# 65_100M-RTL8201.net
KiCad netlist of a schematic drawn in Altium Designer
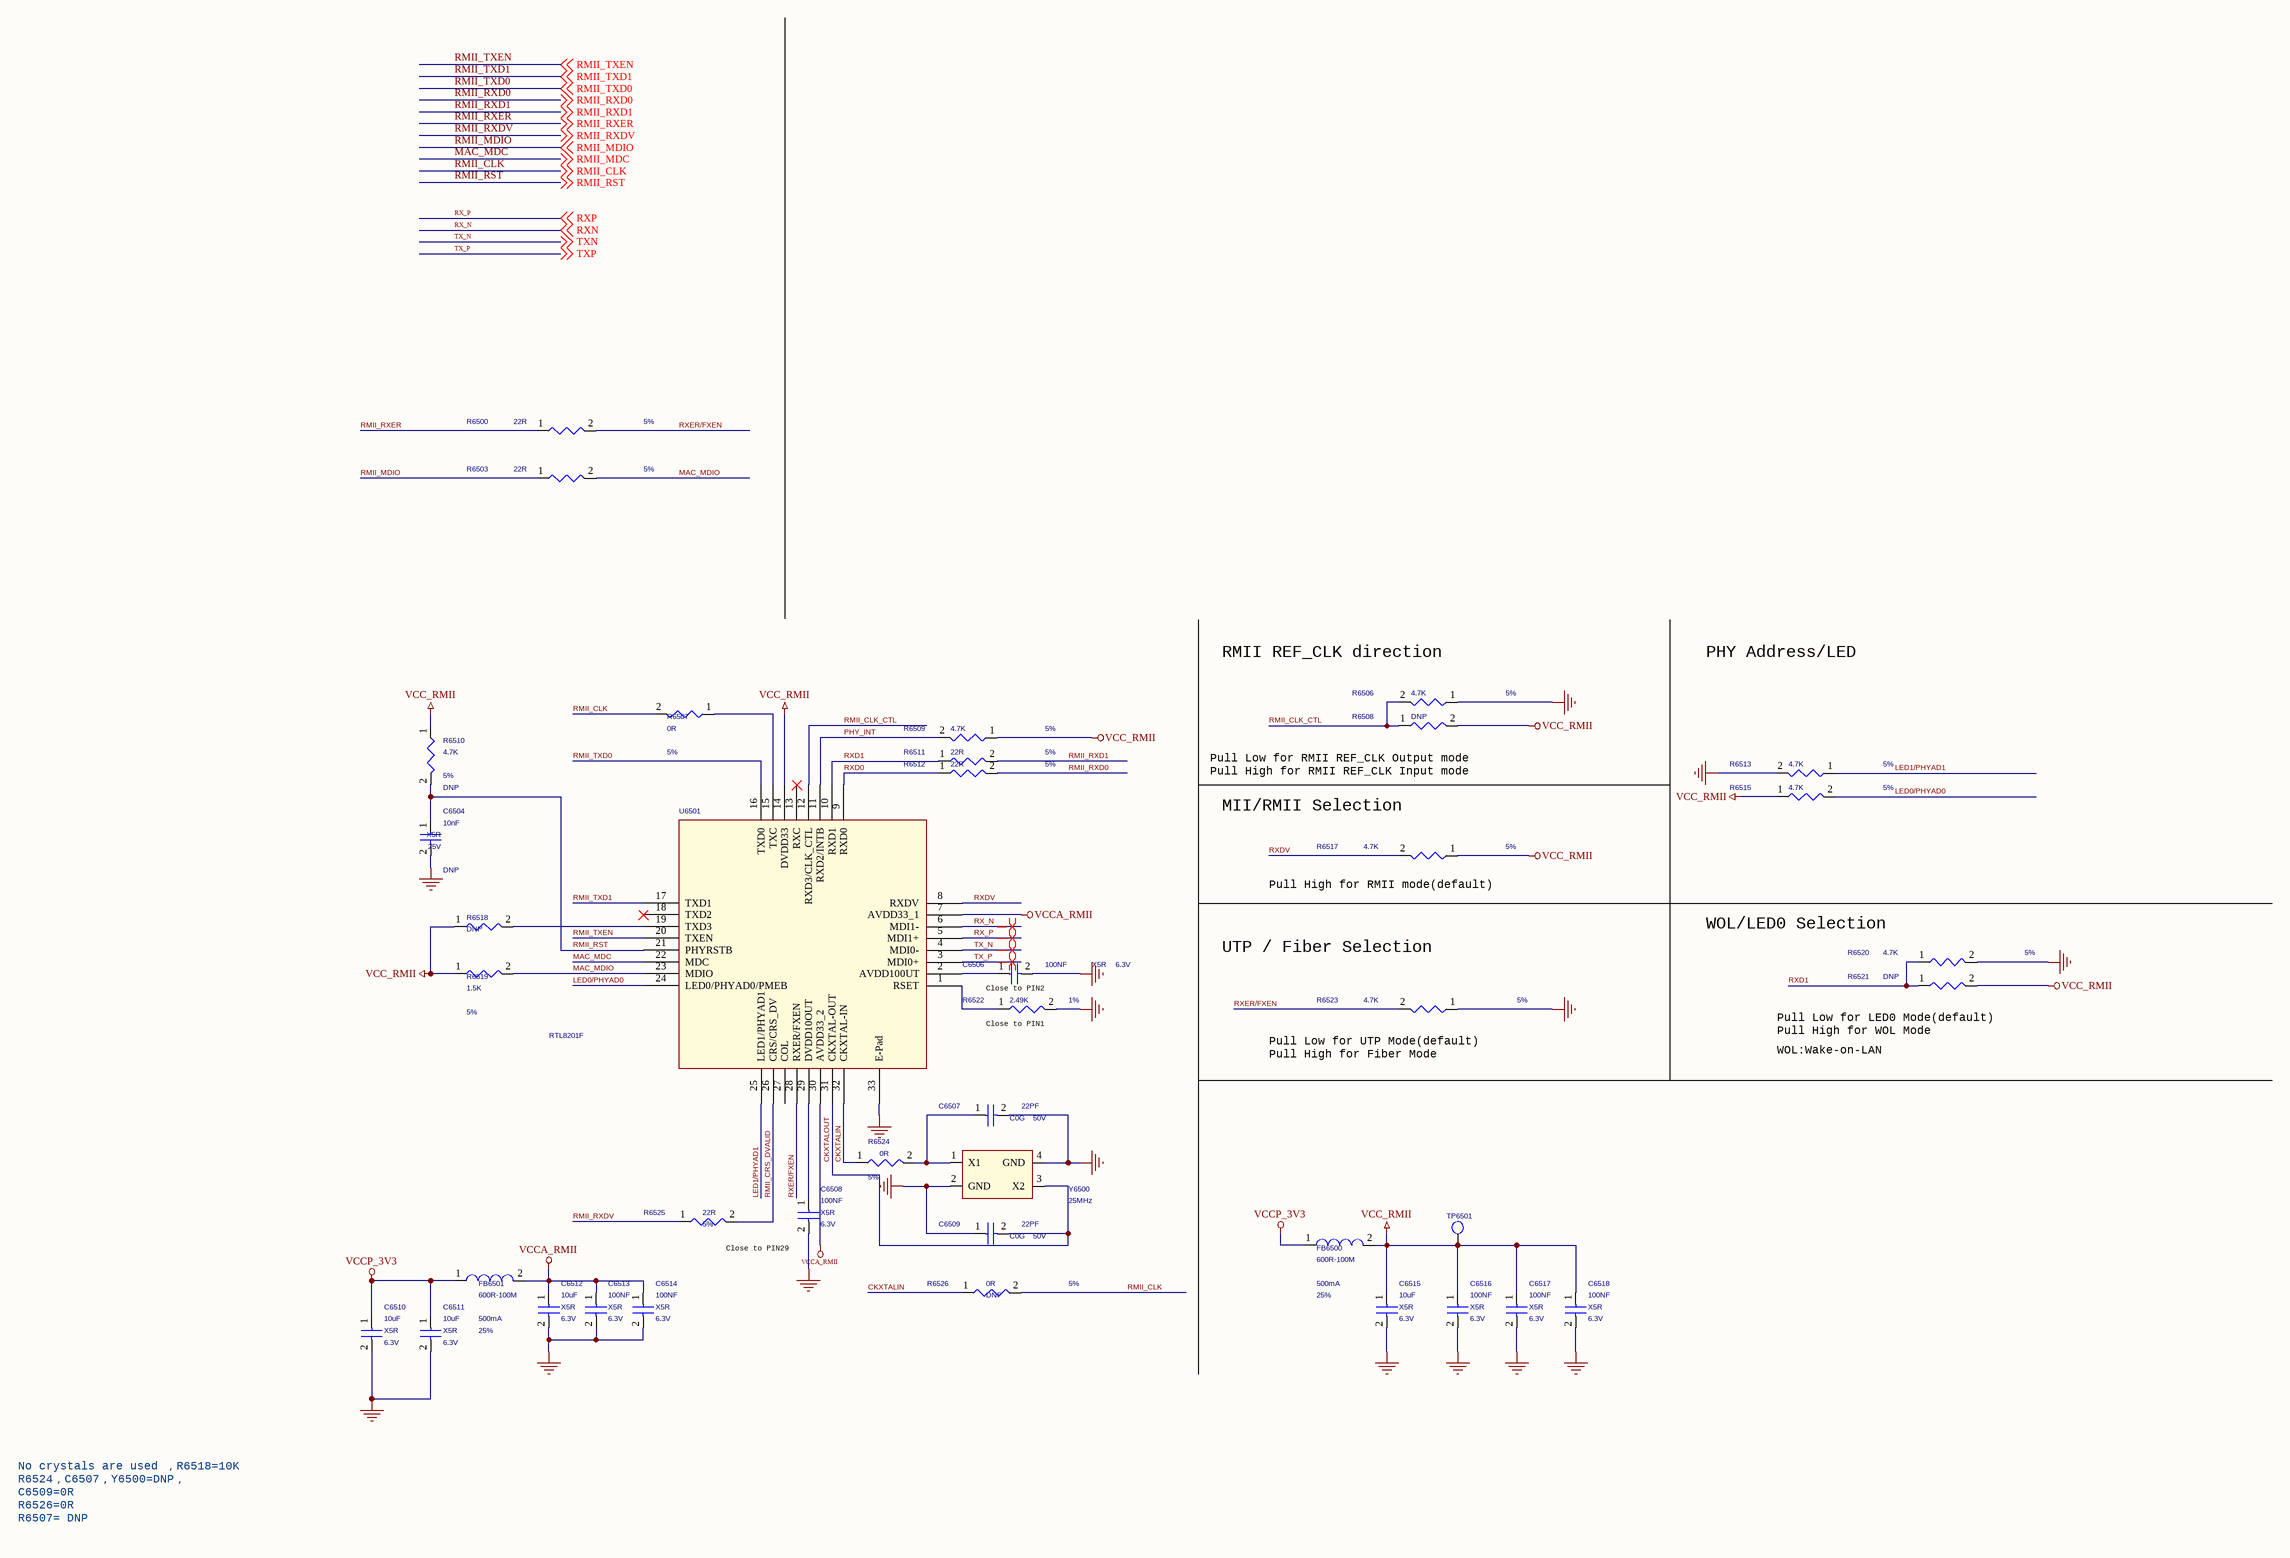
[diagram p0: 65_100M-RTL8201.SchDoc]

(export (version "E")
  (design (tool "Eeschema 10.0.6"))
  (components
    (comp (ref "C6504")
      (value "10nF")
      (footprint "C0402")
      (description "cap,10.00nF,+/-10%,25V,X5R,C0402")
      (fields
        (field (name "VOLTAGE") "25V")
        (field (name "DIELECTRIC") "X5R")
        (field (name "TOLERANCE") "10%")
        (field (name "MANUFACTURER") "TDK")
        (field (name "OPTION") "DNP")
        (field (name "CREATED BY") "JJJ")
      )
      (libsource (lib "*") (part "CAP NP_Dup1"))
    )
    (comp (ref "C6506")
      (value "100NF")
      (footprint "C0402")
      (description "cap,100.00nF,+/-10%,6.3V,X5R,C0402")
      (fields
        (field (name "VOLTAGE") "6.3V")
        (field (name "DIELECTRIC") "X5R")
        (field (name "TOLERANCE") "10%")
        (field (name "MANUFACTURER") "TDK")
        (field (name "CREATED BY") "JJJ")
      )
      (libsource (lib "*") (part "CAP NP_Dup1"))
    )
    (comp (ref "C6507")
      (value "22PF")
      (footprint "C0402")
      (description "cap,22.00pF,+/-2%,50V,C0G,C0402")
      (fields
        (field (name "VOLTAGE") "50V")
        (field (name "DIELECTRIC") "C0G")
        (field (name "TOLERANCE") "2%")
        (field (name "MANUFACTURER") "TDK")
        (field (name "CREATED BY") "JJJ")
      )
      (libsource (lib "*") (part "CAP NP_Dup1"))
    )
    (comp (ref "C6508")
      (value "100NF")
      (footprint "C0402")
      (description "cap,100.00nF,+/-10%,6.3V,X5R,C0402")
      (fields
        (field (name "VOLTAGE") "6.3V")
        (field (name "DIELECTRIC") "X5R")
        (field (name "TOLERANCE") "10%")
        (field (name "MANUFACTURER") "TDK")
        (field (name "CREATED BY") "JJJ")
      )
      (libsource (lib "*") (part "CAP NP_Dup1"))
    )
    (comp (ref "C6509")
      (value "22PF")
      (footprint "C0402")
      (description "cap,22.00pF,+/-2%,50V,C0G,C0402")
      (fields
        (field (name "VOLTAGE") "50V")
        (field (name "DIELECTRIC") "C0G")
        (field (name "MANUFACTURER") "TDK")
        (field (name "TOLERANCE") "2%")
        (field (name "CREATED BY") "JJJ")
      )
      (libsource (lib "*") (part "CAP NP_Dup1"))
    )
    (comp (ref "C6510")
      (value "10uF")
      (footprint "C0603")
      (description "cap,10.00uF,+/-10%,6.3V,X5R,C0603")
      (fields
        (field (name "VOLTAGE") "6.3V")
        (field (name "DIELECTRIC") "X5R")
        (field (name "MANUFACTURER") "TDK")
        (field (name "TOLERANCE") "10%")
        (field (name "CREATED BY") "JJJ")
      )
      (libsource (lib "*") (part "CAP NP_Dup1"))
    )
    (comp (ref "C6511")
      (value "10uF")
      (footprint "C0603")
      (description "cap,10.00uF,+/-10%,6.3V,X5R,C0603")
      (fields
        (field (name "VOLTAGE") "6.3V")
        (field (name "DIELECTRIC") "X5R")
        (field (name "TOLERANCE") "10%")
        (field (name "MANUFACTURER") "TDK")
        (field (name "CREATED BY") "JJJ")
      )
      (libsource (lib "*") (part "CAP NP_Dup1"))
    )
    (comp (ref "C6512")
      (value "10uF")
      (footprint "C0603")
      (description "cap,10.00uF,+/-10%,6.3V,X5R,C0603")
      (fields
        (field (name "VOLTAGE") "6.3V")
        (field (name "DIELECTRIC") "X5R")
        (field (name "TOLERANCE") "10%")
        (field (name "MANUFACTURER") "TDK")
        (field (name "CREATED BY") "JJJ")
      )
      (libsource (lib "*") (part "CAP NP_Dup1"))
    )
    (comp (ref "C6513")
      (value "100NF")
      (footprint "C0402")
      (description "cap,100.00nF,+/-10%,6.3V,X5R,C0402")
      (fields
        (field (name "VOLTAGE") "6.3V")
        (field (name "DIELECTRIC") "X5R")
        (field (name "MANUFACTURER") "TDK")
        (field (name "TOLERANCE") "10%")
        (field (name "CREATED BY") "JJJ")
      )
      (libsource (lib "*") (part "CAP NP_Dup1"))
    )
    (comp (ref "C6514")
      (value "100NF")
      (footprint "C0402")
      (description "cap,100.00nF,+/-10%,6.3V,X5R,C0402")
      (fields
        (field (name "VOLTAGE") "6.3V")
        (field (name "DIELECTRIC") "X5R")
        (field (name "TOLERANCE") "10%")
        (field (name "MANUFACTURER") "TDK")
        (field (name "CREATED BY") "JJJ")
      )
      (libsource (lib "*") (part "CAP NP_Dup1"))
    )
    (comp (ref "C6515")
      (value "10uF")
      (footprint "C0603")
      (description "cap,10.00uF,+/-10%,6.3V,X5R,C0603")
      (fields
        (field (name "VOLTAGE") "6.3V")
        (field (name "DIELECTRIC") "X5R")
        (field (name "MANUFACTURER") "TDK")
        (field (name "TOLERANCE") "10%")
        (field (name "CREATED BY") "JJJ")
      )
      (libsource (lib "*") (part "CAP NP_Dup1"))
    )
    (comp (ref "C6516")
      (value "100NF")
      (footprint "C0402")
      (description "cap,100.00nF,+/-10%,6.3V,X5R,C0402")
      (fields
        (field (name "VOLTAGE") "6.3V")
        (field (name "DIELECTRIC") "X5R")
        (field (name "MANUFACTURER") "TDK")
        (field (name "TOLERANCE") "10%")
        (field (name "CREATED BY") "JJJ")
      )
      (libsource (lib "*") (part "CAP NP_Dup1"))
    )
    (comp (ref "C6517")
      (value "100NF")
      (footprint "C0402")
      (description "cap,100.00nF,+/-10%,6.3V,X5R,C0402")
      (fields
        (field (name "VOLTAGE") "6.3V")
        (field (name "DIELECTRIC") "X5R")
        (field (name "MANUFACTURER") "TDK")
        (field (name "TOLERANCE") "10%")
        (field (name "CREATED BY") "JJJ")
      )
      (libsource (lib "*") (part "CAP NP_Dup1"))
    )
    (comp (ref "C6518")
      (value "100NF")
      (footprint "C0402")
      (description "cap,100.00nF,+/-10%,6.3V,X5R,C0402")
      (fields
        (field (name "VOLTAGE") "6.3V")
        (field (name "DIELECTRIC") "X5R")
        (field (name "MANUFACTURER") "TDK")
        (field (name "TOLERANCE") "10%")
        (field (name "CREATED BY") "JJJ")
      )
      (libsource (lib "*") (part "CAP NP_Dup1"))
    )
    (comp (ref "FB6500")
      (value "600R-100M")
      (footprint "L0603")
      (description "Ferrite Bead,600R-100M,0.25,L0603")
      (fields
        (field (name "IRMS") "500mA")
        (field (name "TOLERANCE") "25%")
        (field (name "MANUFACTURER") "Murata")
        (field (name "CREATED BY") "YTL")
      )
      (libsource (lib "*") (part "BEAD"))
    )
    (comp (ref "FB6501")
      (value "600R-100M")
      (footprint "L0603")
      (description "Ferrite Bead,600R-100M,0.25,L0603")
      (fields
        (field (name "IRMS") "500mA")
        (field (name "TOLERANCE") "25%")
        (field (name "MANUFACTURER") "Murata")
        (field (name "CREATED BY") "YTL")
      )
      (libsource (lib "*") (part "BEAD"))
    )
    (comp (ref "R6500")
      (value "22R")
      (footprint "R0402")
      (description "通用厚膜电阻,22R,+/-5%,R0402,1/16W.")
      (fields
        (field (name "TOLERANCE") "5%")
        (field (name "MANUFACTURER") "YAGEO")
        (field (name "CREATED BY") "YTL")
      )
      (libsource (lib "*") (part "RESISTOR_Dup1"))
    )
    (comp (ref "R6503")
      (value "22R")
      (footprint "R0402")
      (description "通用厚膜电阻,22R,+/-5%,R0402,1/16W.")
      (fields
        (field (name "TOLERANCE") "5%")
        (field (name "MANUFACTURER") "YAGEO")
        (field (name "CREATED BY") "YTL")
      )
      (libsource (lib "*") (part "RESISTOR_Dup1"))
    )
    (comp (ref "R6506")
      (value "4.7K")
      (footprint "R0402")
      (description "通用厚膜电阻,4K7,+/-5%,R0402,1/16W.")
      (fields
        (field (name "TOLERANCE") "5%")
        (field (name "MANUFACTURER") "YAGEO")
        (field (name "CREATED BY") "YTL")
      )
      (libsource (lib "*") (part "RESISTOR_Dup1"))
    )
    (comp (ref "R6507")
      (value "0R")
      (footprint "R0402")
      (description "通用厚膜电阻,0R,+/-5%,R0402,1/16W.")
      (fields
        (field (name "TOLERANCE") "5%")
        (field (name "MANUFACTURER") "YAGEO")
        (field (name "CREATED BY") "YTL")
      )
      (libsource (lib "*") (part "RESISTOR_Dup1"))
    )
    (comp (ref "R6508")
      (value "DNP")
      (footprint "R0402")
      (description "Did Not Place.")
      (fields (field (name "CREATED BY") "JJJ"))
      (libsource (lib "*") (part "RESISTOR_Dup1"))
    )
    (comp (ref "R6509")
      (value "4.7K")
      (footprint "R0402")
      (description "通用厚膜电阻,4K7,+/-5%,R0402,1/16W.")
      (fields
        (field (name "TOLERANCE") "5%")
        (field (name "MANUFACTURER") "YAGEO")
        (field (name "CREATED BY") "YTL")
      )
      (libsource (lib "*") (part "RESISTOR_Dup1"))
    )
    (comp (ref "R6510")
      (value "4.7K")
      (footprint "R0402")
      (description "通用厚膜电阻,4K7,+/-5%,R0402,1/16W.")
      (fields
        (field (name "TOLERANCE") "5%")
        (field (name "MANUFACTURER") "YAGEO")
        (field (name "OPTION") "DNP")
        (field (name "CREATED BY") "YTL")
      )
      (libsource (lib "*") (part "RESISTOR_Dup1"))
    )
    (comp (ref "R6511")
      (value "22R")
      (footprint "R0402")
      (description "通用厚膜电阻,22R,+/-5%,R0402,1/16W.")
      (fields
        (field (name "TOLERANCE") "5%")
        (field (name "MANUFACTURER") "YAGEO")
        (field (name "CREATED BY") "YTL")
      )
      (libsource (lib "*") (part "RESISTOR_Dup1"))
    )
    (comp (ref "R6512")
      (value "22R")
      (footprint "R0402")
      (description "通用厚膜电阻,22R,+/-5%,R0402,1/16W.")
      (fields
        (field (name "TOLERANCE") "5%")
        (field (name "MANUFACTURER") "YAGEO")
        (field (name "CREATED BY") "YTL")
      )
      (libsource (lib "*") (part "RESISTOR_Dup1"))
    )
    (comp (ref "R6513")
      (value "4.7K")
      (footprint "R0402")
      (description "通用厚膜电阻,4K7,+/-5%,R0402,1/16W.")
      (fields
        (field (name "TOLERANCE") "5%")
        (field (name "MANUFACTURER") "YAGEO")
        (field (name "CREATED BY") "YTL")
      )
      (libsource (lib "*") (part "RESISTOR_Dup1"))
    )
    (comp (ref "R6515")
      (value "4.7K")
      (footprint "R0402")
      (description "通用厚膜电阻,4K7,+/-5%,R0402,1/16W.")
      (fields
        (field (name "TOLERANCE") "5%")
        (field (name "MANUFACTURER") "YAGEO")
        (field (name "CREATED BY") "YTL")
      )
      (libsource (lib "*") (part "RESISTOR_Dup1"))
    )
    (comp (ref "R6517")
      (value "4.7K")
      (footprint "R0402")
      (description "通用厚膜电阻,4K7,+/-5%,R0402,1/16W.")
      (fields
        (field (name "TOLERANCE") "5%")
        (field (name "MANUFACTURER") "YAGEO")
        (field (name "CREATED BY") "YTL")
      )
      (libsource (lib "*") (part "RESISTOR_Dup1"))
    )
    (comp (ref "R6518")
      (value "DNP")
      (footprint "R0402")
      (description "Did Not Place.")
      (fields (field (name "CREATED BY") "JJJ"))
      (libsource (lib "*") (part "RESISTOR_Dup1"))
    )
    (comp (ref "R6519")
      (value "1.5K")
      (footprint "R0402")
      (description "通用厚膜电阻,1K5,+/-5%,R0402,1/16W.")
      (fields
        (field (name "TOLERANCE") "5%")
        (field (name "MANUFACTURER") "YAGEO")
        (field (name "CREATED BY") "YTL")
      )
      (libsource (lib "*") (part "RESISTOR_Dup1"))
    )
    (comp (ref "R6520")
      (value "4.7K")
      (footprint "R0402")
      (description "通用厚膜电阻,4K7,+/-5%,R0402,1/16W.")
      (fields
        (field (name "TOLERANCE") "5%")
        (field (name "MANUFACTURER") "YAGEO")
        (field (name "CREATED BY") "YTL")
      )
      (libsource (lib "*") (part "RESISTOR_Dup1"))
    )
    (comp (ref "R6521")
      (value "DNP")
      (footprint "R0402")
      (description "Did Not Place.")
      (fields (field (name "CREATED BY") "JJJ"))
      (libsource (lib "*") (part "RESISTOR_Dup1"))
    )
    (comp (ref "R6522")
      (value "2.49K")
      (footprint "R0402")
      (description "通用厚膜电阻,2K49,+/-1%,R0402,1/16W.")
      (fields
        (field (name "TOLERANCE") "1%")
        (field (name "MANUFACTURER") "YAGEO")
        (field (name "CREATED BY") "YTL")
      )
      (libsource (lib "*") (part "RESISTOR_Dup1"))
    )
    (comp (ref "R6523")
      (value "4.7K")
      (footprint "R0402")
      (description "通用厚膜电阻,4K7,+/-5%,R0402,1/16W.")
      (fields
        (field (name "TOLERANCE") "5%")
        (field (name "MANUFACTURER") "YAGEO")
        (field (name "CREATED BY") "YTL")
      )
      (libsource (lib "*") (part "RESISTOR_Dup1"))
    )
    (comp (ref "R6524")
      (value "0R")
      (footprint "R0402")
      (description "通用厚膜电阻,0R,+/-5%,R0402,1/16W.")
      (fields
        (field (name "TOLERANCE") "5%")
        (field (name "MANUFACTURER") "YAGEO")
        (field (name "CREATED BY") "YTL")
      )
      (libsource (lib "*") (part "RESISTOR_Dup1"))
    )
    (comp (ref "R6525")
      (value "22R")
      (footprint "R0402")
      (description "通用厚膜电阻,22R,+/-5%,R0402,1/16W.")
      (fields
        (field (name "TOLERANCE") "5%")
        (field (name "MANUFACTURER") "YAGEO")
        (field (name "CREATED BY") "YTL")
      )
      (libsource (lib "*") (part "RESISTOR_Dup1"))
    )
    (comp (ref "R6526")
      (value "0R")
      (footprint "R0402")
      (description "通用厚膜电阻,0R,+/-5%,R0402,1/16W.")
      (fields
        (field (name "TOLERANCE") "5%")
        (field (name "MANUFACTURER") "YAGEO")
        (field (name "OPTION") "DNP")
        (field (name "CREATED BY") "YTL")
      )
      (libsource (lib "*") (part "RESISTOR_Dup1"))
    )
    (comp (ref "TP6501")
      (value "TP_0.7")
      (footprint "TEST")
      (description "Test Point 0.7mm")
      (fields (field (name "CREATED BY") "JJJ"))
      (libsource (lib "*") (part "TP"))
    )
    (comp (ref "U6501")
      (value "RTL8201F")
      (footprint "QFN-32_5x5x05P")
      (libsource (lib "*") (part "RTL8201F_0"))
    )
    (comp (ref "Y6500")
      (value "25MHz")
      (footprint "CRY-D3225")
      (description "无源晶振，25M，3225,±10ppm，10pF，Hosonic")
      (fields (field (name "MANUFACTURER") "Hosonic(鸿星电子)") (field (name "CREATED BY") "JJJ"))
      (libsource (lib "*") (part "CRYSTAL_4P"))
    )
  )
  (nets
    (net (code "1") (name "/CKXTALIN") (class "Default")
      (node (ref "R6524") (pin "1") (pinfunction "1_1") (pintype "passive"))
      (node (ref "R6526") (pin "1") (pinfunction "1_1") (pintype "passive"))
      (node (ref "U6501") (pin "32") (pinfunction "CKXTAL-IN_32") (pintype "passive"))
    )
    (net (code "2") (name "/CKXTALOUT") (class "Default")
      (node (ref "C6509") (pin "2") (pinfunction "2_2") (pintype "passive"))
      (node (ref "U6501") (pin "31") (pinfunction "CKXTAL-OUT_31") (pintype "passive"))
      (node (ref "Y6500") (pin "3") (pinfunction "X2_3") (pintype "passive"))
    )
    (net (code "3") (name "/LED0{slash}PHYAD0") (class "Default")
      (node (ref "R6515") (pin "2") (pinfunction "2_2") (pintype "passive"))
      (node (ref "U6501") (pin "24") (pinfunction "LED0/PHYAD0/PMEB_24") (pintype "passive"))
    )
    (net (code "4") (name "/LED1{slash}PHYAD1") (class "Default")
      (node (ref "R6513") (pin "1") (pinfunction "1_1") (pintype "passive"))
      (node (ref "U6501") (pin "25") (pinfunction "LED1/PHYAD1_25") (pintype "passive"))
    )
    (net (code "5") (name "/MAC_MDIO") (class "Default")
      (node (ref "R6503") (pin "2") (pinfunction "2_2") (pintype "passive"))
      (node (ref "R6519") (pin "2") (pinfunction "2_2") (pintype "passive"))
      (node (ref "U6501") (pin "23") (pinfunction "MDIO_23") (pintype "passive"))
    )
    (net (code "6") (name "/PHY_INT") (class "Default")
      (node (ref "R6509") (pin "2") (pinfunction "2_2") (pintype "passive"))
      (node (ref "U6501") (pin "11") (pinfunction "RXD2/INTB_11") (pintype "passive"))
    )
    (net (code "7") (name "/RMII_CLK_CTL") (class "Default")
      (node (ref "R6506") (pin "2") (pinfunction "2_2") (pintype "passive"))
      (node (ref "R6508") (pin "1") (pinfunction "1_1") (pintype "passive"))
      (node (ref "U6501") (pin "12") (pinfunction "RXD3/CLK_CTL_12") (pintype "passive"))
    )
    (net (code "8") (name "/RMII_CRS_DVALID") (class "Default")
      (node (ref "R6525") (pin "2") (pinfunction "2_2") (pintype "passive"))
      (node (ref "U6501") (pin "26") (pinfunction "CRS/CRS_DV_26") (pintype "passive"))
    )
    (net (code "9") (name "/RXD0") (class "Default")
      (node (ref "R6512") (pin "1") (pinfunction "1_1") (pintype "passive"))
      (node (ref "U6501") (pin "9") (pinfunction "RXD0_9") (pintype "passive"))
    )
    (net (code "10") (name "/RXD1") (class "Default")
      (node (ref "R6511") (pin "1") (pinfunction "1_1") (pintype "passive"))
      (node (ref "R6520") (pin "1") (pinfunction "1_1") (pintype "passive"))
      (node (ref "R6521") (pin "1") (pinfunction "1_1") (pintype "passive"))
      (node (ref "U6501") (pin "10") (pinfunction "RXD1_10") (pintype "passive"))
    )
    (net (code "11") (name "/RXDV") (class "Default")
      (node (ref "R6517") (pin "2") (pinfunction "2_2") (pintype "passive"))
      (node (ref "U6501") (pin "8") (pinfunction "RXDV_8") (pintype "passive"))
    )
    (net (code "12") (name "/RXER{slash}FXEN") (class "Default")
      (node (ref "R6500") (pin "2") (pinfunction "2_2") (pintype "passive"))
      (node (ref "R6523") (pin "2") (pinfunction "2_2") (pintype "passive"))
      (node (ref "U6501") (pin "28") (pinfunction "RXER/FXEN_28") (pintype "passive"))
    )
    (net (code "13") (name "GND") (class "Default")
      (node (ref "C6504") (pin "2") (pinfunction "2_2") (pintype "passive"))
      (node (ref "C6506") (pin "2") (pinfunction "2_2") (pintype "passive"))
      (node (ref "C6507") (pin "2") (pinfunction "2_2") (pintype "passive"))
      (node (ref "C6508") (pin "2") (pinfunction "2_2") (pintype "passive"))
      (node (ref "C6509") (pin "1") (pinfunction "1_1") (pintype "passive"))
      (node (ref "C6510") (pin "2") (pinfunction "2_2") (pintype "passive"))
      (node (ref "C6511") (pin "2") (pinfunction "2_2") (pintype "passive"))
      (node (ref "C6512") (pin "2") (pinfunction "2_2") (pintype "passive"))
      (node (ref "C6513") (pin "2") (pinfunction "2_2") (pintype "passive"))
      (node (ref "C6514") (pin "2") (pinfunction "2_2") (pintype "passive"))
      (node (ref "C6515") (pin "2") (pinfunction "2_2") (pintype "passive"))
      (node (ref "C6516") (pin "2") (pinfunction "2_2") (pintype "passive"))
      (node (ref "C6517") (pin "2") (pinfunction "2_2") (pintype "passive"))
      (node (ref "C6518") (pin "2") (pinfunction "2_2") (pintype "passive"))
      (node (ref "R6506") (pin "1") (pinfunction "1_1") (pintype "passive"))
      (node (ref "R6513") (pin "2") (pinfunction "2_2") (pintype "passive"))
      (node (ref "R6520") (pin "2") (pinfunction "2_2") (pintype "passive"))
      (node (ref "R6522") (pin "2") (pinfunction "2_2") (pintype "passive"))
      (node (ref "R6523") (pin "1") (pinfunction "1_1") (pintype "passive"))
      (node (ref "U6501") (pin "33") (pinfunction "E-Pad_33") (pintype "passive"))
      (node (ref "Y6500") (pin "2") (pinfunction "GND_2") (pintype "power_in"))
      (node (ref "Y6500") (pin "4") (pinfunction "GND_4") (pintype "power_in"))
    )
    (net (code "14") (name "Net-(U6501-AVDD100UT)") (class "Default")
      (node (ref "C6506") (pin "1") (pinfunction "1_1") (pintype "passive"))
      (node (ref "U6501") (pin "2") (pinfunction "AVDD100UT_2") (pintype "passive"))
    )
    (net (code "15") (name "Net-(U6501-DVDD10OUT)") (class "Default")
      (node (ref "C6508") (pin "1") (pinfunction "1_1") (pintype "passive"))
      (node (ref "U6501") (pin "29") (pinfunction "DVDD10OUT_29") (pintype "passive"))
    )
    (net (code "16") (name "Net-(U6501-RSET)") (class "Default")
      (node (ref "R6522") (pin "1") (pinfunction "1_1") (pintype "passive"))
      (node (ref "U6501") (pin "1") (pinfunction "RSET_1") (pintype "passive"))
    )
    (net (code "17") (name "Net-(U6501-TXC)") (class "Default")
      (node (ref "R6507") (pin "1") (pinfunction "1_1") (pintype "passive"))
      (node (ref "U6501") (pin "15") (pinfunction "TXC_15") (pintype "passive"))
    )
    (net (code "18") (name "Net-(U6501-TXD3)") (class "Default")
      (node (ref "R6518") (pin "2") (pinfunction "2_2") (pintype "passive"))
      (node (ref "U6501") (pin "19") (pinfunction "TXD3_19") (pintype "passive"))
    )
    (net (code "19") (name "Net-(Y6500-X1)") (class "Default")
      (node (ref "C6507") (pin "1") (pinfunction "1_1") (pintype "passive"))
      (node (ref "R6524") (pin "2") (pinfunction "2_2") (pintype "passive"))
      (node (ref "Y6500") (pin "1") (pinfunction "X1_1") (pintype "passive"))
    )
    (net (code "20") (name "RMII_CLK") (class "Default")
      (node (ref "R6507") (pin "2") (pinfunction "2_2") (pintype "passive"))
      (node (ref "R6526") (pin "2") (pinfunction "2_2") (pintype "passive"))
    )
    (net (code "21") (name "RMII_MDC") (class "Default")
      (node (ref "U6501") (pin "22") (pinfunction "MDC_22") (pintype "passive"))
    )
    (net (code "22") (name "RMII_MDIO") (class "Default")
      (node (ref "R6503") (pin "1") (pinfunction "1_1") (pintype "passive"))
    )
    (net (code "23") (name "RMII_RST") (class "Default")
      (node (ref "C6504") (pin "1") (pinfunction "1_1") (pintype "passive"))
      (node (ref "R6510") (pin "2") (pinfunction "2_2") (pintype "passive"))
      (node (ref "U6501") (pin "21") (pinfunction "PHYRSTB_21") (pintype "passive"))
    )
    (net (code "24") (name "RMII_RXD0") (class "Default")
      (node (ref "R6512") (pin "2") (pinfunction "2_2") (pintype "passive"))
    )
    (net (code "25") (name "RMII_RXD1") (class "Default")
      (node (ref "R6511") (pin "2") (pinfunction "2_2") (pintype "passive"))
    )
    (net (code "26") (name "RMII_RXDV") (class "Default")
      (node (ref "R6525") (pin "1") (pinfunction "1_1") (pintype "passive"))
    )
    (net (code "27") (name "RMII_RXER") (class "Default")
      (node (ref "R6500") (pin "1") (pinfunction "1_1") (pintype "passive"))
    )
    (net (code "28") (name "RMII_TXD0") (class "Default")
      (node (ref "U6501") (pin "16") (pinfunction "TXD0_16") (pintype "passive"))
    )
    (net (code "29") (name "RMII_TXD1") (class "Default")
      (node (ref "U6501") (pin "17") (pinfunction "TXD1_17") (pintype "passive"))
    )
    (net (code "30") (name "RMII_TXEN") (class "Default")
      (node (ref "U6501") (pin "20") (pinfunction "TXEN_20") (pintype "passive"))
    )
    (net (code "31") (name "RXN") (class "Default")
      (node (ref "U6501") (pin "6") (pinfunction "MDI1-_6") (pintype "passive"))
    )
    (net (code "32") (name "RXP") (class "Default")
      (node (ref "U6501") (pin "5") (pinfunction "MDI1+_5") (pintype "passive"))
    )
    (net (code "33") (name "TXN") (class "Default")
      (node (ref "U6501") (pin "4") (pinfunction "MDI0-_4") (pintype "passive"))
    )
    (net (code "34") (name "TXP") (class "Default")
      (node (ref "U6501") (pin "3") (pinfunction "MDI0+_3") (pintype "passive"))
    )
    (net (code "35") (name "VCCA_RMII") (class "Default")
      (node (ref "C6512") (pin "1") (pinfunction "1_1") (pintype "passive"))
      (node (ref "C6513") (pin "1") (pinfunction "1_1") (pintype "passive"))
      (node (ref "C6514") (pin "1") (pinfunction "1_1") (pintype "passive"))
      (node (ref "FB6501") (pin "2") (pinfunction "2_2") (pintype "passive"))
      (node (ref "U6501") (pin "30") (pinfunction "AVDD33_2_30") (pintype "passive"))
      (node (ref "U6501") (pin "7") (pinfunction "AVDD33_1_7") (pintype "passive"))
    )
    (net (code "36") (name "VCCP_3V3") (class "Default")
      (node (ref "C6510") (pin "1") (pinfunction "1_1") (pintype "passive"))
      (node (ref "C6511") (pin "1") (pinfunction "1_1") (pintype "passive"))
      (node (ref "FB6500") (pin "1") (pinfunction "1_1") (pintype "passive"))
      (node (ref "FB6501") (pin "1") (pinfunction "1_1") (pintype "passive"))
    )
    (net (code "37") (name "VCC_RMII") (class "Default")
      (node (ref "C6515") (pin "1") (pinfunction "1_1") (pintype "passive"))
      (node (ref "C6516") (pin "1") (pinfunction "1_1") (pintype "passive"))
      (node (ref "C6517") (pin "1") (pinfunction "1_1") (pintype "passive"))
      (node (ref "C6518") (pin "1") (pinfunction "1_1") (pintype "passive"))
      (node (ref "FB6500") (pin "2") (pinfunction "2_2") (pintype "passive"))
      (node (ref "R6508") (pin "2") (pinfunction "2_2") (pintype "passive"))
      (node (ref "R6509") (pin "1") (pinfunction "1_1") (pintype "passive"))
      (node (ref "R6510") (pin "1") (pinfunction "1_1") (pintype "passive"))
      (node (ref "R6515") (pin "1") (pinfunction "1_1") (pintype "passive"))
      (node (ref "R6517") (pin "1") (pinfunction "1_1") (pintype "passive"))
      (node (ref "R6518") (pin "1") (pinfunction "1_1") (pintype "passive"))
      (node (ref "R6519") (pin "1") (pinfunction "1_1") (pintype "passive"))
      (node (ref "R6521") (pin "2") (pinfunction "2_2") (pintype "passive"))
      (node (ref "TP6501") (pin "1") (pinfunction "1_1") (pintype "passive"))
      (node (ref "U6501") (pin "14") (pinfunction "DVDD33_14") (pintype "passive"))
    )
    (net (code "38") (name "unconnected-(U6501-COL-Pad27)") (class "Default")
      (node (ref "U6501") (pin "27") (pinfunction "COL_27") (pintype "passive"))
    )
    (net (code "39") (name "unconnected-(U6501-RXC-Pad13)") (class "Default")
      (node (ref "U6501") (pin "13") (pinfunction "RXC_13") (pintype "passive+no_connect"))
    )
    (net (code "40") (name "unconnected-(U6501-TXD2-Pad18)") (class "Default")
      (node (ref "U6501") (pin "18") (pinfunction "TXD2_18") (pintype "passive+no_connect"))
    )
  )
)
